# Sheet1.net
KiCad netlist of a schematic drawn in Altium Designer
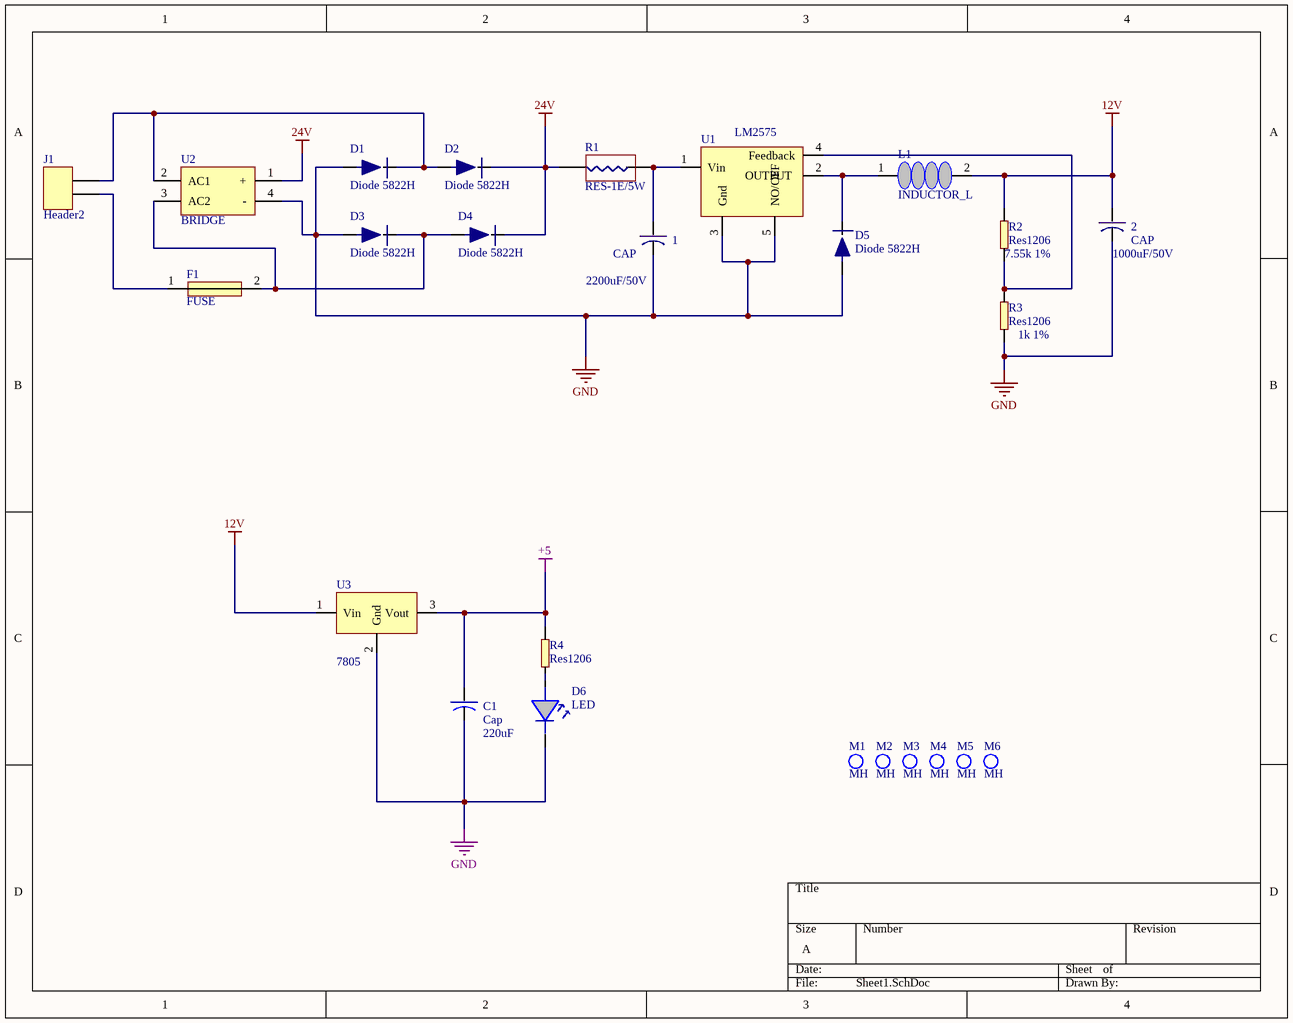
[diagram p0: Sheet1.SchDoc]

(export (version "E")
  (design (tool "Eeschema 10.0.6"))
  (components
    (comp (ref "1")
      (value "CAP")
      (footprint "Capacitor - 2200uF")
      (fields (field (name "ALTIUM_VALUE") "2200uF/50V"))
      (libsource (lib "VIJAYIntegrated_Library") (part "2200uF/50V"))
    )
    (comp (ref "2")
      (value "CAP")
      (footprint "Capacitor1000uF")
      (fields (field (name "ALTIUM_VALUE") "1000uF/50V"))
      (libsource (lib "VIJAYIntegrated_Library") (part "2200uF/50V"))
    )
    (comp (ref "C1")
      (value "Cap")
      (footprint "CAP_220uF")
      (description "Cap_220uF")
      (fields (field (name "ALTIUM_UNNAMED_1") "220uF"))
      (libsource (lib "Dinesh_New_Integrated_Library") (part "CAP_220uF"))
    )
    (comp (ref "D1")
      (value "Diode 5822H")
      (footprint "Diode")
      (libsource (lib "VIJAYIntegrated_Library") (part "Diode 5822H"))
    )
    (comp (ref "D2")
      (value "Diode 5822H")
      (footprint "Diode")
      (libsource (lib "VIJAYIntegrated_Library") (part "Diode 5822H"))
    )
    (comp (ref "D3")
      (value "Diode 5822H")
      (footprint "Diode")
      (libsource (lib "VIJAYIntegrated_Library") (part "Diode 5822H"))
    )
    (comp (ref "D4")
      (value "Diode 5822H")
      (footprint "Diode")
      (libsource (lib "VIJAYIntegrated_Library") (part "Diode 5822H"))
    )
    (comp (ref "D5")
      (value "Diode 5822H")
      (footprint "Diode")
      (libsource (lib "VIJAYIntegrated_Library") (part "Diode 5822H"))
    )
    (comp (ref "D6")
      (value "LED")
      (footprint "LED5MM")
      (description "LED_5MM")
      (libsource (lib "Dinesh_New_Integrated_Library") (part "LED_5MM"))
    )
    (comp (ref "F1")
      (value "FUSE")
      (footprint "FUSE")
      (description "Fuse")
      (libsource (lib "Dinesh_New_Integrated_Library") (part "FUSE"))
    )
    (comp (ref "J1")
      (value "Header2")
      (footprint "Header2")
      (libsource (lib "VIJAYIntegrated_Library") (part "Header2"))
    )
    (comp (ref "L1")
      (value "INDUCTOR_L")
      (footprint "inductor-200mil")
      (description "Inductor-200")
      (libsource (lib "VIJAYIntegrated_Library") (part "Inductor-200"))
    )
    (comp (ref "M1")
      (value "MH")
      (footprint "Mounting hole")
      (libsource (lib "Dinesh_New_Integrated_Library") (part "MH"))
    )
    (comp (ref "M2")
      (value "MH")
      (footprint "Mounting hole")
      (libsource (lib "Dinesh_New_Integrated_Library") (part "MH"))
    )
    (comp (ref "M3")
      (value "MH")
      (footprint "Mounting hole")
      (libsource (lib "Dinesh_New_Integrated_Library") (part "MH"))
    )
    (comp (ref "M4")
      (value "MH")
      (footprint "Mounting hole")
      (libsource (lib "Dinesh_New_Integrated_Library") (part "MH"))
    )
    (comp (ref "M5")
      (value "MH")
      (footprint "Mounting hole")
      (libsource (lib "Dinesh_New_Integrated_Library") (part "MH"))
    )
    (comp (ref "M6")
      (value "MH")
      (footprint "Mounting hole")
      (libsource (lib "Dinesh_New_Integrated_Library") (part "MH"))
    )
    (comp (ref "R1")
      (value "RES-1E/5W")
      (footprint "RES-1E/5W")
      (libsource (lib "VIJAYIntegrated_Library") (part "RES-1E/5W"))
    )
    (comp (ref "R2")
      (value "Res1206")
      (footprint "1206")
      (fields (field (name "ALTIUM_VALUE") "7.55k 1%"))
      (libsource (lib "Dinesh_New_Integrated_Library") (part "Res1206"))
    )
    (comp (ref "R3")
      (value "Res1206")
      (footprint "1206")
      (fields (field (name "ALTIUM_VALUE") "1k 1%"))
      (libsource (lib "Dinesh_New_Integrated_Library") (part "Res1206"))
    )
    (comp (ref "R4")
      (value "Res1206")
      (footprint "1206")
      (libsource (lib "Dinesh_New_Integrated_Library") (part "Res1206"))
    )
    (comp (ref "U1")
      (value "LM2575")
      (footprint "D2PAK_5PIN")
      (description "Vol Reg")
      (libsource (lib "Dinesh_New_Integrated_Library") (part "LM2575"))
    )
    (comp (ref "U2")
      (value "BRIDGE")
      (footprint "BRIDGE_200MIL")
      (libsource (lib "Dinesh_New_Integrated_Library") (part "BRIDGE"))
    )
    (comp (ref "U3")
      (value "7805")
      (footprint "D-PAK")
      (description "Vol Reg")
      (libsource (lib "Dinesh_New_Integrated_Library") (part "7805"))
    )
  )
  (nets
    (net (code "1") (name "+5") (class "Default")
      (node (ref "C1") (pin "1") (pinfunction "a_1") (pintype "passive"))
      (node (ref "R4") (pin "2") (pinfunction "b_2") (pintype "passive"))
      (node (ref "U3") (pin "3") (pinfunction "Vout_3") (pintype "passive"))
    )
    (net (code "2") (name "12V") (class "Default")
      (node (ref "2") (pin "1") (pinfunction "a_1") (pintype "passive"))
      (node (ref "L1") (pin "2") (pinfunction "b_2") (pintype "passive"))
      (node (ref "R2") (pin "2") (pinfunction "b_2") (pintype "passive"))
      (node (ref "U3") (pin "1") (pinfunction "Vin_1") (pintype "passive"))
    )
    (net (code "3") (name "24V") (class "Default")
      (node (ref "D2") (pin "2") (pinfunction "2_2") (pintype "passive"))
      (node (ref "D4") (pin "2") (pinfunction "2_2") (pintype "passive"))
      (node (ref "R1") (pin "1") (pinfunction "1_1") (pintype "passive"))
      (node (ref "U2") (pin "1") (pinfunction "+_1") (pintype "passive"))
    )
    (net (code "4") (name "GND") (class "Default")
      (node (ref "1") (pin "2") (pinfunction "b_2") (pintype "passive"))
      (node (ref "2") (pin "2") (pinfunction "b_2") (pintype "passive"))
      (node (ref "C1") (pin "2") (pinfunction "b_2") (pintype "passive"))
      (node (ref "D1") (pin "1") (pinfunction "1_1") (pintype "passive"))
      (node (ref "D3") (pin "1") (pinfunction "1_1") (pintype "passive"))
      (node (ref "D5") (pin "1") (pinfunction "1_1") (pintype "passive"))
      (node (ref "D6") (pin "2") (pinfunction "B_2") (pintype "passive"))
      (node (ref "R3") (pin "1") (pinfunction "a_1") (pintype "passive"))
      (node (ref "U1") (pin "3") (pinfunction "Gnd_3") (pintype "passive"))
      (node (ref "U1") (pin "5") (pinfunction "NO/OFF_5") (pintype "passive"))
      (node (ref "U2") (pin "4") (pinfunction "-_4") (pintype "passive"))
      (node (ref "U3") (pin "2") (pinfunction "Gnd_2") (pintype "passive"))
    )
    (net (code "5") (name "Net-(1-a)") (class "Default")
      (node (ref "1") (pin "1") (pinfunction "a_1") (pintype "passive"))
      (node (ref "R1") (pin "2") (pinfunction "2_2") (pintype "passive"))
      (node (ref "U1") (pin "1") (pinfunction "Vin_1") (pintype "passive"))
    )
    (net (code "6") (name "Net-(D6-A)") (class "Default")
      (node (ref "D6") (pin "1") (pinfunction "A_1") (pintype "passive"))
      (node (ref "R4") (pin "1") (pinfunction "a_1") (pintype "passive"))
    )
    (net (code "7") (name "Net-(F1-A)") (class "Default")
      (node (ref "F1") (pin "1") (pinfunction "A_1") (pintype "passive"))
      (node (ref "J1") (pin "1") (pinfunction "1_1") (pintype "power_in"))
    )
    (net (code "8") (name "Net-(F1-B)") (class "Default")
      (node (ref "D3") (pin "2") (pinfunction "2_2") (pintype "passive"))
      (node (ref "D4") (pin "1") (pinfunction "1_1") (pintype "passive"))
      (node (ref "F1") (pin "2") (pinfunction "B_2") (pintype "passive"))
      (node (ref "U2") (pin "3") (pinfunction "AC2_3") (pintype "passive"))
    )
    (net (code "9") (name "Net-(L1-a)") (class "Default")
      (node (ref "D5") (pin "2") (pinfunction "2_2") (pintype "passive"))
      (node (ref "L1") (pin "1") (pinfunction "a_1") (pintype "passive"))
      (node (ref "U1") (pin "2") (pinfunction "OUTPUT_2") (pintype "passive"))
    )
    (net (code "10") (name "Net-(R2-a)") (class "Default")
      (node (ref "R2") (pin "1") (pinfunction "a_1") (pintype "passive"))
      (node (ref "R3") (pin "2") (pinfunction "b_2") (pintype "passive"))
      (node (ref "U1") (pin "4") (pinfunction "Feedback_4") (pintype "passive"))
    )
    (net (code "11") (name "Net-(U2-AC1)") (class "Default")
      (node (ref "D1") (pin "2") (pinfunction "2_2") (pintype "passive"))
      (node (ref "D2") (pin "1") (pinfunction "1_1") (pintype "passive"))
      (node (ref "J1") (pin "2") (pinfunction "2_2") (pintype "power_in"))
      (node (ref "U2") (pin "2") (pinfunction "AC1_2") (pintype "passive"))
    )
  )
)
